# STM8S003F3P6.net
KiCad netlist of a schematic drawn in Altium Designer
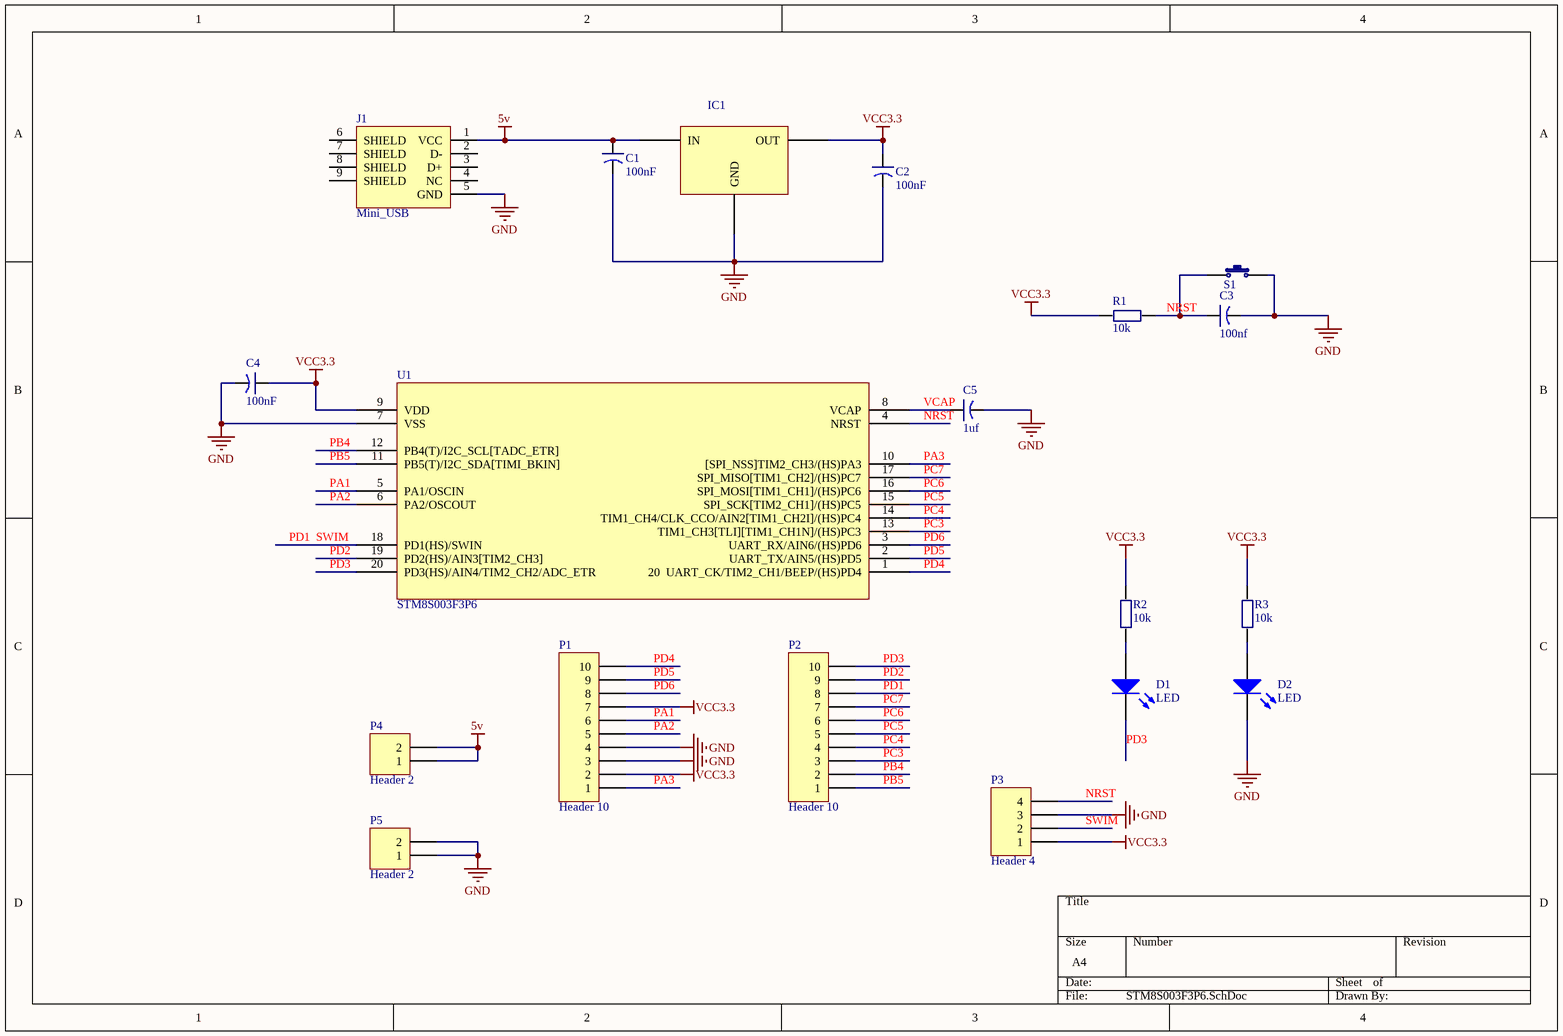
[diagram p0: STM8S003F3P6.SchDoc]

(export (version "E")
  (design (tool "Eeschema 10.0.6"))
  (components
    (comp (ref "C1")
      (value "100nF")
      (footprint "C0805")
      (fields (field (name "Comment") "Capacitor"))
      (libsource (lib "My Devices") (part "Capacitor"))
    )
    (comp (ref "C2")
      (value "100nF")
      (footprint "C0805")
      (fields (field (name "Comment") "Capacitor"))
      (libsource (lib "My Devices") (part "Capacitor"))
    )
    (comp (ref "C3")
      (value "100nf")
      (footprint "C0805")
      (fields (field (name "Comment") "Capacitor"))
      (libsource (lib "My Devices") (part "Capacitor"))
    )
    (comp (ref "C4")
      (value "100nF")
      (footprint "C0805")
      (fields (field (name "Comment") "Capacitor"))
      (libsource (lib "My Devices") (part "Capacitor"))
    )
    (comp (ref "C5")
      (value "1uf")
      (footprint "C0805")
      (fields (field (name "Comment") "Capacitor"))
      (libsource (lib "My Devices") (part "Capacitor"))
    )
    (comp (ref "D1") (value "LED") (footprint "0805D") (libsource (lib "My Devices") (part "LED")))
    (comp (ref "D2") (value "LED") (footprint "0805D") (libsource (lib "My Devices") (part "LED")))
    (comp (ref "IC1") (value "ASM1117") (footprint "SOT-223") (libsource (lib "电源类集成库") (part "ASM1117")))
    (comp (ref "J1")
      (value "Mini_USB")
      (footprint "Mini_USB")
      (libsource (lib "My Devices") (part "Mini_USB"))
    )
    (comp (ref "P1")
      (value "Header 10")
      (footprint "HDR1X10")
      (description "Header, 10-Pin")
      (fields (field (name "PUBLISHER") "Altium Limited"))
      (libsource (lib "Header Devices") (part "Header 10"))
    )
    (comp (ref "P2")
      (value "Header 10")
      (footprint "HDR1X10")
      (description "Header, 10-Pin")
      (fields (field (name "PUBLISHER") "Altium Limited"))
      (libsource (lib "Header Devices") (part "Header 10"))
    )
    (comp (ref "P3")
      (value "Header 4")
      (footprint "HDR1X4")
      (description "Header, 4-Pin")
      (fields (field (name "PUBLISHER") "Altium Limited"))
      (libsource (lib "Header Devices") (part "Header 4"))
    )
    (comp (ref "P4")
      (value "Header 2")
      (footprint "HDR1X2")
      (description "Header, 2-Pin")
      (fields (field (name "PUBLISHER") "Altium Limited"))
      (libsource (lib "Header Devices") (part "Header 2"))
    )
    (comp (ref "P5")
      (value "Header 2")
      (footprint "HDR1X2")
      (description "Header, 2-Pin")
      (fields (field (name "PUBLISHER") "Altium Limited"))
      (libsource (lib "Header Devices") (part "Header 2"))
    )
    (comp (ref "R1")
      (value "10k")
      (footprint "R0805")
      (fields (field (name "Comment") "Resistor"))
      (libsource (lib "My Devices") (part "Resistor"))
    )
    (comp (ref "R2")
      (value "10k")
      (footprint "R0805")
      (fields (field (name "Comment") "Resistor"))
      (libsource (lib "My Devices") (part "Resistor"))
    )
    (comp (ref "R3")
      (value "10k")
      (footprint "R0805")
      (fields (field (name "Comment") "Resistor"))
      (libsource (lib "My Devices") (part "Resistor"))
    )
    (comp (ref "S1") (value "Switch") (footprint "TD-19XA") (libsource (lib "My Devices") (part "Switch")))
    (comp (ref "U1")
      (value "STM8S003F3P6")
      (footprint "STM8S003F3P6")
      (libsource (lib "电机驱动元器件") (part "STM8S003F3P6"))
    )
  )
  (nets
    (net (code "1") (name "/NRST") (class "Default")
      (node (ref "C3") (pin "1") (pinfunction "0_1") (pintype "passive"))
      (node (ref "P3") (pin "4") (pinfunction "4_4") (pintype "passive"))
      (node (ref "R1") (pin "1") (pintype "passive"))
      (node (ref "S1") (pin "1") (pinfunction "0_1") (pintype "passive"))
      (node (ref "U1") (pin "4") (pinfunction "NRST_4") (pintype "passive"))
    )
    (net (code "2") (name "/PA1") (class "Default")
      (node (ref "P1") (pin "6") (pinfunction "6_6") (pintype "passive"))
      (node (ref "U1") (pin "5") (pinfunction "PA1/OSCIN_5") (pintype "passive"))
    )
    (net (code "3") (name "/PA2") (class "Default")
      (node (ref "P1") (pin "5") (pinfunction "5_5") (pintype "passive"))
      (node (ref "U1") (pin "6") (pinfunction "PA2/OSCOUT_6") (pintype "passive"))
    )
    (net (code "4") (name "/PA3") (class "Default")
      (node (ref "P1") (pin "1") (pinfunction "1_1") (pintype "passive"))
      (node (ref "U1") (pin "10") (pinfunction "[SPI_NSS]TIM2_CH3/(HS)PA3_10") (pintype "passive"))
    )
    (net (code "5") (name "/PB4") (class "Default")
      (node (ref "P2") (pin "2") (pinfunction "2_2") (pintype "passive"))
      (node (ref "U1") (pin "12") (pinfunction "PB4(T)/I2C_SCL[TADC_ETR]_12") (pintype "passive"))
    )
    (net (code "6") (name "/PB5") (class "Default")
      (node (ref "P2") (pin "1") (pinfunction "1_1") (pintype "passive"))
      (node (ref "U1") (pin "11") (pinfunction "PB5(T)/I2C_SDA[TIMI_BKIN]_11") (pintype "passive"))
    )
    (net (code "7") (name "/PC3") (class "Default")
      (node (ref "P2") (pin "3") (pinfunction "3_3") (pintype "passive"))
      (node (ref "U1") (pin "13") (pinfunction "TIM1_CH3[TLI][TIM1_CH1N]/(HS)PC3_13") (pintype "passive"))
    )
    (net (code "8") (name "/PC4") (class "Default")
      (node (ref "P2") (pin "4") (pinfunction "4_4") (pintype "passive"))
      (node (ref "U1") (pin "14") (pinfunction "TIM1_CH4/CLK_CCO/AIN2[TIM1_CH2I]/(HS)PC4_14") (pintype "passive"))
    )
    (net (code "9") (name "/PC5") (class "Default")
      (node (ref "P2") (pin "5") (pinfunction "5_5") (pintype "passive"))
      (node (ref "U1") (pin "15") (pinfunction "SPI_SCK[TIM2_CH1]/(HS)PC5_15") (pintype "passive"))
    )
    (net (code "10") (name "/PC6") (class "Default")
      (node (ref "P2") (pin "6") (pinfunction "6_6") (pintype "passive"))
      (node (ref "U1") (pin "16") (pinfunction "SPI_MOSI[TIM1_CH1]/(HS)PC6_16") (pintype "passive"))
    )
    (net (code "11") (name "/PC7") (class "Default")
      (node (ref "P2") (pin "7") (pinfunction "7_7") (pintype "passive"))
      (node (ref "U1") (pin "17") (pinfunction "SPI_MISO[TIM1_CH2]/(HS)PC7_17") (pintype "passive"))
    )
    (net (code "12") (name "/PD1") (class "Default")
      (node (ref "P2") (pin "8") (pinfunction "8_8") (pintype "passive"))
      (node (ref "P3") (pin "2") (pinfunction "2_2") (pintype "passive"))
      (node (ref "U1") (pin "18") (pinfunction "PD1(HS)/SWIN_18") (pintype "passive"))
    )
    (net (code "13") (name "/PD2") (class "Default")
      (node (ref "P2") (pin "9") (pinfunction "9_9") (pintype "passive"))
      (node (ref "U1") (pin "19") (pinfunction "PD2(HS)/AIN3[TIM2_CH3]_19") (pintype "passive"))
    )
    (net (code "14") (name "/PD3") (class "Default")
      (node (ref "D1") (pin "2") (pinfunction "K_2") (pintype "passive"))
      (node (ref "P2") (pin "10") (pinfunction "10_10") (pintype "passive"))
      (node (ref "U1") (pin "20") (pinfunction "PD3(HS)/AIN4/TIM2_CH2/ADC_ETR_20") (pintype "passive"))
    )
    (net (code "15") (name "/PD4") (class "Default")
      (node (ref "P1") (pin "10") (pinfunction "10_10") (pintype "passive"))
      (node (ref "U1") (pin "1") (pinfunction "20__UART_CK/TIM2_CH1/BEEP/(HS)PD4_1") (pintype "passive"))
    )
    (net (code "16") (name "/PD5") (class "Default")
      (node (ref "P1") (pin "9") (pinfunction "9_9") (pintype "passive"))
      (node (ref "U1") (pin "2") (pinfunction "UART_TX/AIN5/(HS)PD5_2") (pintype "passive"))
    )
    (net (code "17") (name "/PD6") (class "Default")
      (node (ref "P1") (pin "8") (pinfunction "8_8") (pintype "passive"))
      (node (ref "U1") (pin "3") (pinfunction "UART_RX/AIN6/(HS)PD6_3") (pintype "passive"))
    )
    (net (code "18") (name "/VCAP") (class "Default")
      (node (ref "C5") (pin "1") (pinfunction "0_1") (pintype "passive"))
      (node (ref "U1") (pin "8") (pinfunction "VCAP_8") (pintype "passive"))
    )
    (net (code "19") (name "5v") (class "Default")
      (node (ref "C1") (pin "1") (pinfunction "0_1") (pintype "passive"))
      (node (ref "IC1") (pin "3") (pinfunction "IN_3") (pintype "passive"))
      (node (ref "J1") (pin "1") (pinfunction "VCC_1") (pintype "passive"))
      (node (ref "P4") (pin "1") (pinfunction "1_1") (pintype "passive"))
      (node (ref "P4") (pin "2") (pinfunction "2_2") (pintype "passive"))
    )
    (net (code "20") (name "GND") (class "Default")
      (node (ref "C1") (pin "2") (pinfunction "1_2") (pintype "passive"))
      (node (ref "C2") (pin "2") (pinfunction "1_2") (pintype "passive"))
      (node (ref "C3") (pin "2") (pinfunction "1_2") (pintype "passive"))
      (node (ref "C4") (pin "2") (pinfunction "1_2") (pintype "passive"))
      (node (ref "C5") (pin "2") (pinfunction "1_2") (pintype "passive"))
      (node (ref "D2") (pin "2") (pinfunction "K_2") (pintype "passive"))
      (node (ref "IC1") (pin "1") (pinfunction "GND_1") (pintype "passive"))
      (node (ref "J1") (pin "5") (pinfunction "GND_5") (pintype "passive"))
      (node (ref "P1") (pin "3") (pinfunction "3_3") (pintype "passive"))
      (node (ref "P1") (pin "4") (pinfunction "4_4") (pintype "passive"))
      (node (ref "P3") (pin "3") (pinfunction "3_3") (pintype "passive"))
      (node (ref "P5") (pin "1") (pinfunction "1_1") (pintype "passive"))
      (node (ref "P5") (pin "2") (pinfunction "2_2") (pintype "passive"))
      (node (ref "S1") (pin "2") (pinfunction "1_2") (pintype "passive"))
      (node (ref "U1") (pin "7") (pinfunction "VSS_7") (pintype "passive"))
    )
    (net (code "21") (name "Net-(D1-A)") (class "Default")
      (node (ref "D1") (pin "1") (pinfunction "A_1") (pintype "passive"))
      (node (ref "R2") (pin "1") (pintype "passive"))
    )
    (net (code "22") (name "Net-(D2-A)") (class "Default")
      (node (ref "D2") (pin "1") (pinfunction "A_1") (pintype "passive"))
      (node (ref "R3") (pin "1") (pintype "passive"))
    )
    (net (code "23") (name "VCC3.3") (class "Default")
      (node (ref "C2") (pin "1") (pinfunction "0_1") (pintype "passive"))
      (node (ref "C4") (pin "1") (pinfunction "0_1") (pintype "passive"))
      (node (ref "IC1") (pin "2") (pinfunction "OUT_2") (pintype "passive"))
      (node (ref "P1") (pin "2") (pinfunction "2_2") (pintype "passive"))
      (node (ref "P1") (pin "7") (pinfunction "7_7") (pintype "passive"))
      (node (ref "P3") (pin "1") (pinfunction "1_1") (pintype "passive"))
      (node (ref "R1") (pin "2") (pintype "passive"))
      (node (ref "R2") (pin "2") (pintype "passive"))
      (node (ref "R3") (pin "2") (pintype "passive"))
      (node (ref "U1") (pin "9") (pinfunction "VDD_9") (pintype "passive"))
    )
    (net (code "24") (name "unconnected-(J1-D+-Pad3)") (class "Default")
      (node (ref "J1") (pin "3") (pinfunction "D+_3") (pintype "passive"))
    )
    (net (code "25") (name "unconnected-(J1-D--Pad2)") (class "Default")
      (node (ref "J1") (pin "2") (pinfunction "D-_2") (pintype "passive"))
    )
    (net (code "26") (name "unconnected-(J1-NC-Pad4)") (class "Default")
      (node (ref "J1") (pin "4") (pinfunction "NC_4") (pintype "passive"))
    )
    (net (code "27") (name "unconnected-(J1-SHIELD-Pad6)") (class "Default")
      (node (ref "J1") (pin "6") (pinfunction "SHIELD_6") (pintype "passive"))
    )
    (net (code "28") (name "unconnected-(J1-SHIELD-Pad7)") (class "Default")
      (node (ref "J1") (pin "7") (pinfunction "SHIELD_7") (pintype "passive"))
    )
    (net (code "29") (name "unconnected-(J1-SHIELD-Pad8)") (class "Default")
      (node (ref "J1") (pin "8") (pinfunction "SHIELD_8") (pintype "passive"))
    )
    (net (code "30") (name "unconnected-(J1-SHIELD-Pad9)") (class "Default")
      (node (ref "J1") (pin "9") (pinfunction "SHIELD_9") (pintype "passive"))
    )
  )
)
